# rly410.net
KiCad netlist of a schematic drawn in EAGLE
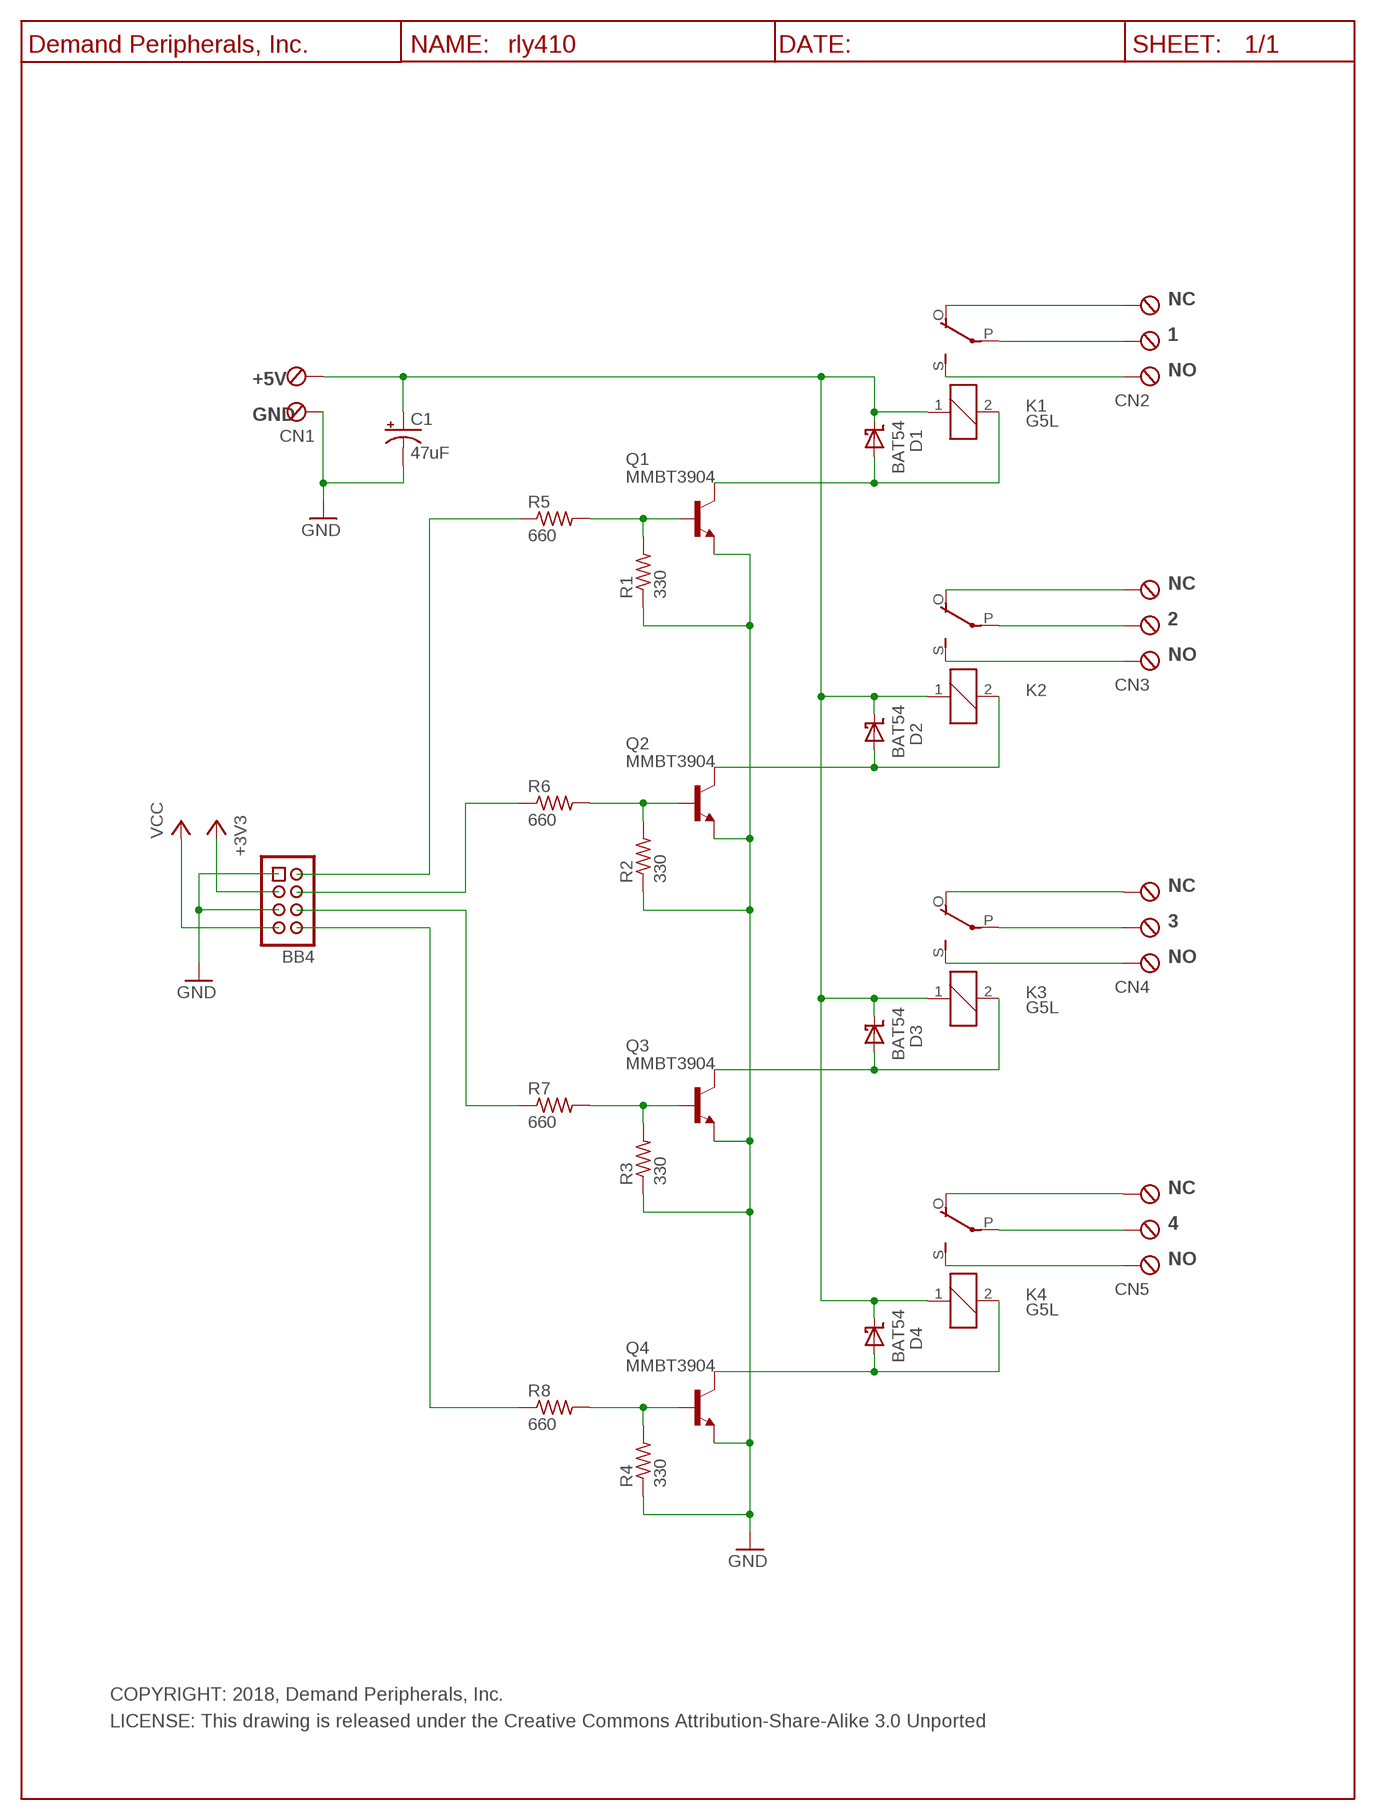
[diagram p0: schematic, sheet 1]

(export (version "E")
  (design (tool "Eeschema 10.0.6"))
  (components
    (comp (ref "BB4")
      (value "Keyed_Pin_Header_4x2(0.1\"x0.1\")")
      (footprint "eagle-import:HDR-4X2")
      (libsource (lib "eagle-import") (part "HDR-4X2-SHR"))
    )
    (comp (ref "C1")
      (value "47uF")
      (footprint "eagle-import:E3.5-8")
      (libsource (lib "eagle-import") (part "C100UF_E3.5-8"))
    )
    (comp (ref "CN1")
      (value "TBLK-5.08-X2")
      (footprint "eagle-import:TBLK-5.08-X2")
      (libsource (lib "eagle-import") (part "TBLK-5.08-X2"))
    )
    (comp (ref "CN2")
      (value "TBLK-5.08-X3")
      (footprint "eagle-import:TBLK-5.08-X3")
      (libsource (lib "eagle-import") (part "TBLK-5.08-X3"))
    )
    (comp (ref "CN3")
      (value "TBLK-5.08-X3")
      (footprint "eagle-import:TBLK-5.08-X3")
      (libsource (lib "eagle-import") (part "TBLK-5.08-X3"))
    )
    (comp (ref "CN4")
      (value "TBLK-5.08-X3")
      (footprint "eagle-import:TBLK-5.08-X3")
      (libsource (lib "eagle-import") (part "TBLK-5.08-X3"))
    )
    (comp (ref "CN5")
      (value "TBLK-5.08-X3")
      (footprint "eagle-import:TBLK-5.08-X3")
      (libsource (lib "eagle-import") (part "TBLK-5.08-X3"))
    )
    (comp (ref "D1")
      (value "BAT54")
      (footprint "eagle-import:SOT23")
      (libsource (lib "eagle-import") (part "BAT54"))
    )
    (comp (ref "D2")
      (value "BAT54")
      (footprint "eagle-import:SOT23")
      (libsource (lib "eagle-import") (part "BAT54"))
    )
    (comp (ref "D3")
      (value "BAT54")
      (footprint "eagle-import:SOT23")
      (libsource (lib "eagle-import") (part "BAT54"))
    )
    (comp (ref "D4")
      (value "BAT54")
      (footprint "eagle-import:SOT23")
      (libsource (lib "eagle-import") (part "BAT54"))
    )
    (comp (ref "K1")
      (value "G5L")
      (footprint "eagle-import:G5LE")
      (libsource (lib "eagle-import") (part "G5L"))
    )
    (comp (ref "K2")
      (value "G5L")
      (footprint "eagle-import:G5LE")
      (libsource (lib "eagle-import") (part "G5L"))
    )
    (comp (ref "K3")
      (value "G5L")
      (footprint "eagle-import:G5LE")
      (libsource (lib "eagle-import") (part "G5L"))
    )
    (comp (ref "K4")
      (value "G5L")
      (footprint "eagle-import:G5LE")
      (libsource (lib "eagle-import") (part "G5L"))
    )
    (comp (ref "Q1")
      (value "MMBT3904")
      (footprint "eagle-import:SOT23")
      (libsource (lib "eagle-import") (part "MMBT3904"))
    )
    (comp (ref "Q2")
      (value "MMBT3904")
      (footprint "eagle-import:SOT23")
      (libsource (lib "eagle-import") (part "MMBT3904"))
    )
    (comp (ref "Q3")
      (value "MMBT3904")
      (footprint "eagle-import:SOT23")
      (libsource (lib "eagle-import") (part "MMBT3904"))
    )
    (comp (ref "Q4")
      (value "MMBT3904")
      (footprint "eagle-import:SOT23")
      (libsource (lib "eagle-import") (part "MMBT3904"))
    )
    (comp (ref "R1")
      (value "330")
      (footprint "eagle-import:R0603")
      (libsource (lib "eagle-import") (part "R360_R0603"))
    )
    (comp (ref "R2")
      (value "330")
      (footprint "eagle-import:R0603")
      (libsource (lib "eagle-import") (part "R360_R0603"))
    )
    (comp (ref "R3")
      (value "330")
      (footprint "eagle-import:R0603")
      (libsource (lib "eagle-import") (part "R360_R0603"))
    )
    (comp (ref "R4")
      (value "330")
      (footprint "eagle-import:R0603")
      (libsource (lib "eagle-import") (part "R360_R0603"))
    )
    (comp (ref "R5")
      (value "660")
      (footprint "eagle-import:R0603")
      (libsource (lib "eagle-import") (part "R660_R0603"))
    )
    (comp (ref "R6")
      (value "660")
      (footprint "eagle-import:R0603")
      (libsource (lib "eagle-import") (part "R660_R0603"))
    )
    (comp (ref "R7")
      (value "660")
      (footprint "eagle-import:R0603")
      (libsource (lib "eagle-import") (part "R660_R0603"))
    )
    (comp (ref "R8")
      (value "660")
      (footprint "eagle-import:R0603")
      (libsource (lib "eagle-import") (part "R660_R0603"))
    )
    (comp (ref "U$1")
      (value "DP_FRAME_P")
      (footprint "eagle-import:P_FRAME")
      (libsource (lib "eagle-import") (part "DP_FRAME_P"))
    )
  )
  (nets
    (net (code "1") (name "+3V3") (class "Default")
      (node (ref "BB4") (pin "3") (pinfunction "3_3") (pintype "passive"))
    )
    (net (code "2") (name "GND") (class "Default")
      (node (ref "BB4") (pin "1") (pinfunction "1_1") (pintype "passive"))
      (node (ref "BB4") (pin "5") (pinfunction "5_5") (pintype "passive"))
      (node (ref "C1") (pin "-") (pinfunction "-_-") (pintype "passive"))
      (node (ref "CN1") (pin "1") (pinfunction "KL_1") (pintype "passive"))
      (node (ref "Q1") (pin "2") (pinfunction "E_2") (pintype "passive"))
      (node (ref "Q2") (pin "2") (pinfunction "E_2") (pintype "passive"))
      (node (ref "Q3") (pin "2") (pinfunction "E_2") (pintype "passive"))
      (node (ref "Q4") (pin "2") (pinfunction "E_2") (pintype "passive"))
      (node (ref "R1") (pin "1") (pinfunction "1_1") (pintype "passive"))
      (node (ref "R2") (pin "1") (pinfunction "1_1") (pintype "passive"))
      (node (ref "R3") (pin "1") (pinfunction "1_1") (pintype "passive"))
      (node (ref "R4") (pin "1") (pinfunction "1_1") (pintype "passive"))
    )
    (net (code "3") (name "Net-(BB4-Pad2)") (class "Default")
      (node (ref "BB4") (pin "2") (pinfunction "2_2") (pintype "passive"))
      (node (ref "R5") (pin "1") (pinfunction "1_1") (pintype "passive"))
    )
    (net (code "4") (name "Net-(BB4-Pad4)") (class "Default")
      (node (ref "BB4") (pin "4") (pinfunction "4_4") (pintype "passive"))
      (node (ref "R6") (pin "1") (pinfunction "1_1") (pintype "passive"))
    )
    (net (code "5") (name "Net-(BB4-Pad6)") (class "Default")
      (node (ref "BB4") (pin "6") (pinfunction "6_6") (pintype "passive"))
      (node (ref "R7") (pin "1") (pinfunction "1_1") (pintype "passive"))
    )
    (net (code "6") (name "Net-(BB4-Pad8)") (class "Default")
      (node (ref "BB4") (pin "8") (pinfunction "8_8") (pintype "passive"))
      (node (ref "R8") (pin "1") (pinfunction "1_1") (pintype "passive"))
    )
    (net (code "7") (name "Net-(CN1-KL1)") (class "Default")
      (node (ref "C1") (pin "+") (pinfunction "+_+") (pintype "passive"))
      (node (ref "CN1") (pin "2") (pinfunction "KL1_2") (pintype "passive"))
      (node (ref "D1") (pin "3") (pinfunction "CC_3") (pintype "passive"))
      (node (ref "D2") (pin "3") (pinfunction "CC_3") (pintype "passive"))
      (node (ref "D3") (pin "3") (pinfunction "CC_3") (pintype "passive"))
      (node (ref "D4") (pin "3") (pinfunction "CC_3") (pintype "passive"))
      (node (ref "K1") (pin "1") (pinfunction "1_1") (pintype "passive"))
      (node (ref "K2") (pin "1") (pinfunction "1_1") (pintype "passive"))
      (node (ref "K3") (pin "1") (pinfunction "1_1") (pintype "passive"))
      (node (ref "K4") (pin "1") (pinfunction "1_1") (pintype "passive"))
    )
    (net (code "8") (name "Net-(CN2-KL)") (class "Default")
      (node (ref "CN2") (pin "1") (pinfunction "KL_1") (pintype "passive"))
      (node (ref "K1") (pin "S") (pinfunction "S_S") (pintype "passive"))
    )
    (net (code "9") (name "Net-(CN2-KL1)") (class "Default")
      (node (ref "CN2") (pin "2") (pinfunction "KL1_2") (pintype "passive"))
      (node (ref "K1") (pin "P") (pinfunction "P_P") (pintype "passive"))
    )
    (net (code "10") (name "Net-(CN2-KL2)") (class "Default")
      (node (ref "CN2") (pin "3") (pinfunction "KL2_3") (pintype "passive"))
      (node (ref "K1") (pin "O") (pinfunction "O_O") (pintype "passive"))
    )
    (net (code "11") (name "Net-(CN3-KL)") (class "Default")
      (node (ref "CN3") (pin "1") (pinfunction "KL_1") (pintype "passive"))
      (node (ref "K2") (pin "S") (pinfunction "S_S") (pintype "passive"))
    )
    (net (code "12") (name "Net-(CN3-KL1)") (class "Default")
      (node (ref "CN3") (pin "2") (pinfunction "KL1_2") (pintype "passive"))
      (node (ref "K2") (pin "P") (pinfunction "P_P") (pintype "passive"))
    )
    (net (code "13") (name "Net-(CN3-KL2)") (class "Default")
      (node (ref "CN3") (pin "3") (pinfunction "KL2_3") (pintype "passive"))
      (node (ref "K2") (pin "O") (pinfunction "O_O") (pintype "passive"))
    )
    (net (code "14") (name "Net-(CN4-KL)") (class "Default")
      (node (ref "CN4") (pin "1") (pinfunction "KL_1") (pintype "passive"))
      (node (ref "K3") (pin "S") (pinfunction "S_S") (pintype "passive"))
    )
    (net (code "15") (name "Net-(CN4-KL1)") (class "Default")
      (node (ref "CN4") (pin "2") (pinfunction "KL1_2") (pintype "passive"))
      (node (ref "K3") (pin "P") (pinfunction "P_P") (pintype "passive"))
    )
    (net (code "16") (name "Net-(CN4-KL2)") (class "Default")
      (node (ref "CN4") (pin "3") (pinfunction "KL2_3") (pintype "passive"))
      (node (ref "K3") (pin "O") (pinfunction "O_O") (pintype "passive"))
    )
    (net (code "17") (name "Net-(CN5-KL)") (class "Default")
      (node (ref "CN5") (pin "1") (pinfunction "KL_1") (pintype "passive"))
      (node (ref "K4") (pin "S") (pinfunction "S_S") (pintype "passive"))
    )
    (net (code "18") (name "Net-(CN5-KL1)") (class "Default")
      (node (ref "CN5") (pin "2") (pinfunction "KL1_2") (pintype "passive"))
      (node (ref "K4") (pin "P") (pinfunction "P_P") (pintype "passive"))
    )
    (net (code "19") (name "Net-(CN5-KL2)") (class "Default")
      (node (ref "CN5") (pin "3") (pinfunction "KL2_3") (pintype "passive"))
      (node (ref "K4") (pin "O") (pinfunction "O_O") (pintype "passive"))
    )
    (net (code "20") (name "Net-(D1-A)") (class "Default")
      (node (ref "D1") (pin "1") (pinfunction "A_1") (pintype "passive"))
      (node (ref "K1") (pin "2") (pinfunction "2_2") (pintype "passive"))
      (node (ref "Q1") (pin "3") (pinfunction "C_3") (pintype "passive"))
    )
    (net (code "21") (name "Net-(D2-A)") (class "Default")
      (node (ref "D2") (pin "1") (pinfunction "A_1") (pintype "passive"))
      (node (ref "K2") (pin "2") (pinfunction "2_2") (pintype "passive"))
      (node (ref "Q2") (pin "3") (pinfunction "C_3") (pintype "passive"))
    )
    (net (code "22") (name "Net-(D3-A)") (class "Default")
      (node (ref "D3") (pin "1") (pinfunction "A_1") (pintype "passive"))
      (node (ref "K3") (pin "2") (pinfunction "2_2") (pintype "passive"))
      (node (ref "Q3") (pin "3") (pinfunction "C_3") (pintype "passive"))
    )
    (net (code "23") (name "Net-(D4-A)") (class "Default")
      (node (ref "D4") (pin "1") (pinfunction "A_1") (pintype "passive"))
      (node (ref "K4") (pin "2") (pinfunction "2_2") (pintype "passive"))
      (node (ref "Q4") (pin "3") (pinfunction "C_3") (pintype "passive"))
    )
    (net (code "24") (name "Net-(Q1-B)") (class "Default")
      (node (ref "Q1") (pin "1") (pinfunction "B_1") (pintype "passive"))
      (node (ref "R1") (pin "2") (pinfunction "2_2") (pintype "passive"))
      (node (ref "R5") (pin "2") (pinfunction "2_2") (pintype "passive"))
    )
    (net (code "25") (name "Net-(Q2-B)") (class "Default")
      (node (ref "Q2") (pin "1") (pinfunction "B_1") (pintype "passive"))
      (node (ref "R2") (pin "2") (pinfunction "2_2") (pintype "passive"))
      (node (ref "R6") (pin "2") (pinfunction "2_2") (pintype "passive"))
    )
    (net (code "26") (name "Net-(Q3-B)") (class "Default")
      (node (ref "Q3") (pin "1") (pinfunction "B_1") (pintype "passive"))
      (node (ref "R3") (pin "2") (pinfunction "2_2") (pintype "passive"))
      (node (ref "R7") (pin "2") (pinfunction "2_2") (pintype "passive"))
    )
    (net (code "27") (name "Net-(Q4-B)") (class "Default")
      (node (ref "Q4") (pin "1") (pinfunction "B_1") (pintype "passive"))
      (node (ref "R4") (pin "2") (pinfunction "2_2") (pintype "passive"))
      (node (ref "R8") (pin "2") (pinfunction "2_2") (pintype "passive"))
    )
    (net (code "28") (name "VCC") (class "Default")
      (node (ref "BB4") (pin "7") (pinfunction "7_7") (pintype "passive"))
    )
  )
)
